# Power.net
KiCad netlist of a schematic drawn in Altium Designer
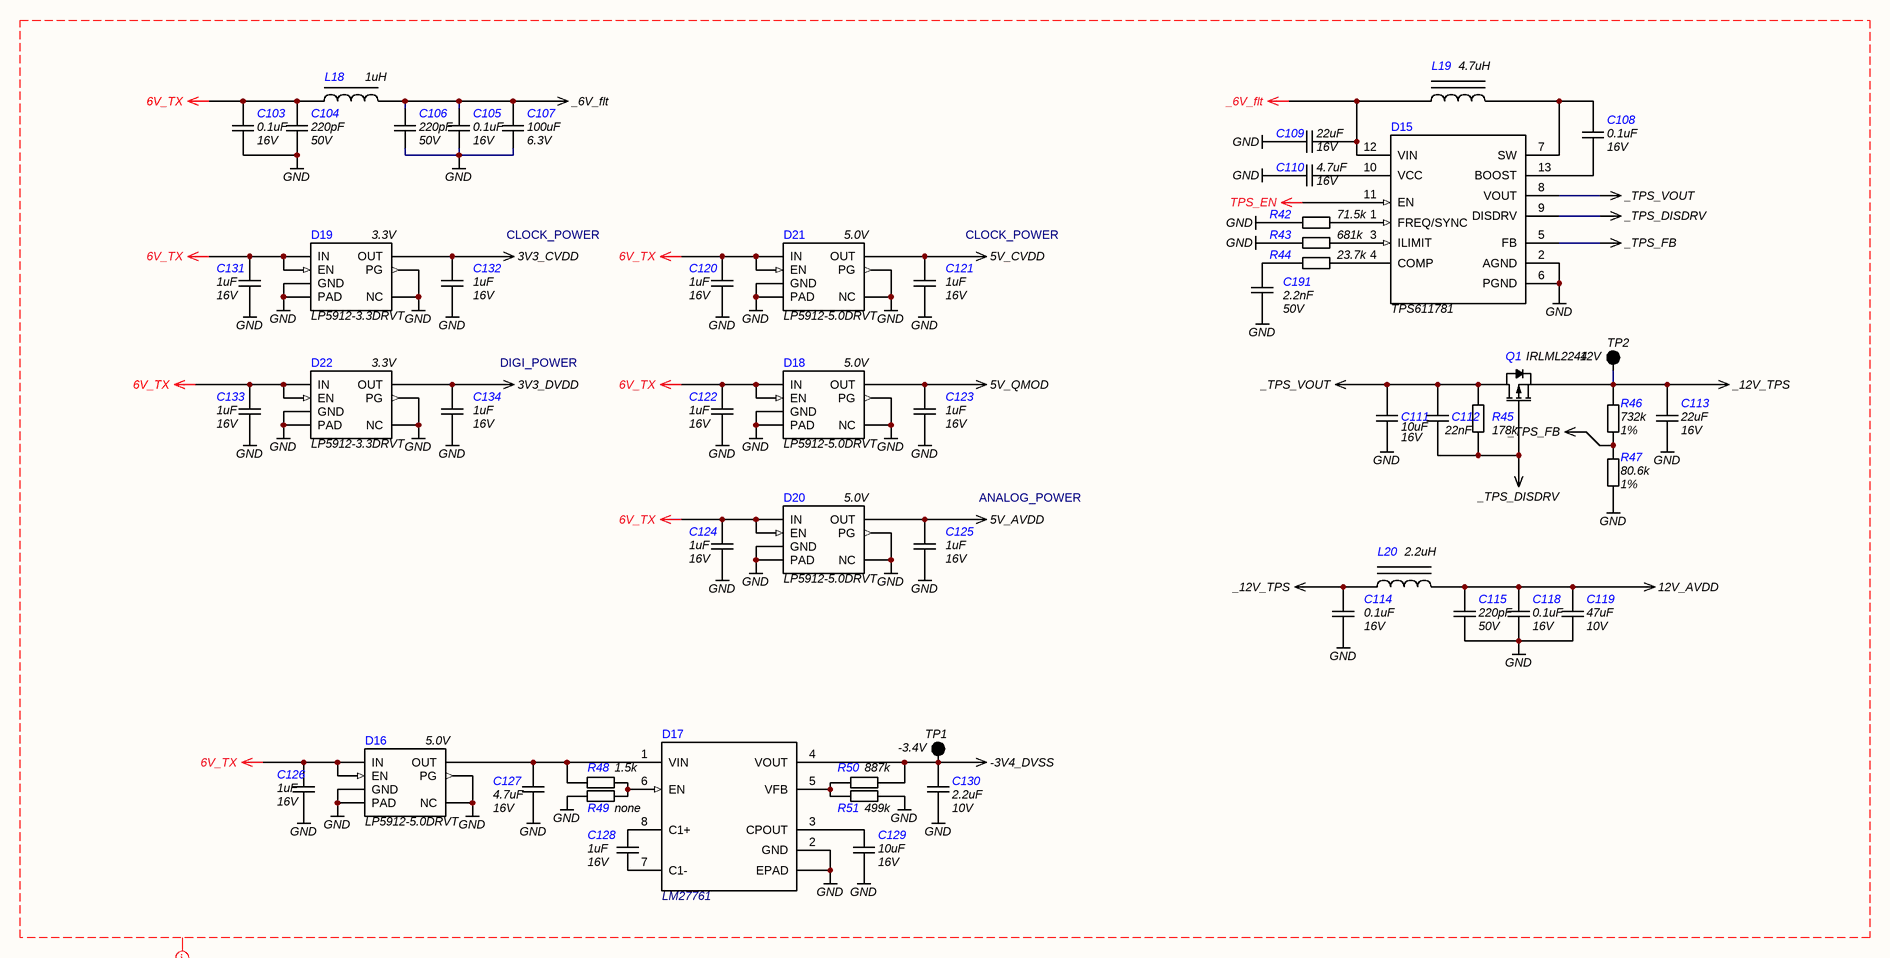
[diagram p0: Power.SchDoc]

(export (version "E")
  (design (tool "Eeschema 10.0.6"))
  (components
    (comp (ref "C103")
      (value "0.1uF")
      (footprint "C0402")
      (description "SMD Capacitor")
      (fields
        (field (name "MANUFACTURER") "Murata")
        (field (name "TOLERANCE") "10%")
        (field (name "VOLTAGE") "16V")
      )
      (libsource (lib "Kintex_SDR") (part "CAP"))
    )
    (comp (ref "C104")
      (value "220pF")
      (footprint "C0603")
      (description "SMD Capacitor")
      (fields
        (field (name "MANUFACTURER") "Kemet")
        (field (name "TOLERANCE") "10%")
        (field (name "VOLTAGE") "50V")
      )
      (libsource (lib "Kintex_SDR") (part "CAP"))
    )
    (comp (ref "C105")
      (value "0.1uF")
      (footprint "C0402")
      (description "SMD Capacitor")
      (fields
        (field (name "MANUFACTURER") "Murata")
        (field (name "TOLERANCE") "10%")
        (field (name "VOLTAGE") "16V")
      )
      (libsource (lib "Kintex_SDR") (part "CAP"))
    )
    (comp (ref "C106")
      (value "220pF")
      (footprint "C0603")
      (description "SMD Capacitor")
      (fields
        (field (name "MANUFACTURER") "Kemet")
        (field (name "TOLERANCE") "10%")
        (field (name "VOLTAGE") "50V")
      )
      (libsource (lib "Kintex_SDR") (part "CAP"))
    )
    (comp (ref "C107")
      (value "100uF")
      (footprint "C1210")
      (description "SMD Capacitor")
      (fields
        (field (name "MANUFACTURER") "Murata")
        (field (name "TOLERANCE") "20%")
        (field (name "VOLTAGE") "6.3V")
      )
      (libsource (lib "Kintex_SDR") (part "CAP uF"))
    )
    (comp (ref "C108")
      (value "0.1uF")
      (footprint "C0402")
      (description "SMD Capacitor")
      (fields
        (field (name "MANUFACTURER") "Murata")
        (field (name "TOLERANCE") "10%")
        (field (name "VOLTAGE") "16V")
      )
      (libsource (lib "Kintex_SDR") (part "CAP"))
    )
    (comp (ref "C109")
      (value "22uF")
      (footprint "C0805")
      (description "SMD Capacitor")
      (fields
        (field (name "MANUFACTURER") "Murata")
        (field (name "TOLERANCE") "±20%")
        (field (name "VOLTAGE") "16V")
      )
      (libsource (lib "Kintex_SDR") (part "CAP uF"))
    )
    (comp (ref "C110")
      (value "4.7uF")
      (footprint "C0603")
      (description "SMD Capacitor")
      (fields
        (field (name "MANUFACTURER") "Samsung")
        (field (name "TOLERANCE") "10%")
        (field (name "VOLTAGE") "16V")
      )
      (libsource (lib "Kintex_SDR") (part "CAP"))
    )
    (comp (ref "C111")
      (value "10uF")
      (footprint "C0805")
      (description "SMD Capacitor")
      (fields
        (field (name "MANUFACTURER") "Murata")
        (field (name "TOLERANCE") "±10%")
        (field (name "VOLTAGE") "16V")
      )
      (libsource (lib "Kintex_SDR") (part "CAP uF"))
    )
    (comp (ref "C112")
      (value "22nF")
      (footprint "C0402")
      (description "SMD Capacitor")
      (fields (field (name "MANUFACTURER") "Murata") (field (name "TOLERANCE") "10%"))
      (libsource (lib "Kintex_SDR") (part "CAP"))
    )
    (comp (ref "C113")
      (value "22uF")
      (footprint "C0805")
      (description "SMD Capacitor")
      (fields
        (field (name "MANUFACTURER") "Murata")
        (field (name "TOLERANCE") "±20%")
        (field (name "VOLTAGE") "16V")
      )
      (libsource (lib "Kintex_SDR") (part "CAP uF"))
    )
    (comp (ref "C114")
      (value "0.1uF")
      (footprint "C0402")
      (description "SMD Capacitor")
      (fields
        (field (name "MANUFACTURER") "Murata")
        (field (name "TOLERANCE") "10%")
        (field (name "VOLTAGE") "16V")
      )
      (libsource (lib "Kintex_SDR") (part "CAP"))
    )
    (comp (ref "C115")
      (value "220pF")
      (footprint "C0603")
      (description "SMD Capacitor")
      (fields
        (field (name "MANUFACTURER") "Kemet")
        (field (name "TOLERANCE") "10%")
        (field (name "VOLTAGE") "50V")
      )
      (libsource (lib "Kintex_SDR") (part "CAP"))
    )
    (comp (ref "C118")
      (value "0.1uF")
      (footprint "C0402")
      (description "SMD Capacitor")
      (fields
        (field (name "MANUFACTURER") "Murata")
        (field (name "TOLERANCE") "10%")
        (field (name "VOLTAGE") "16V")
      )
      (libsource (lib "Kintex_SDR") (part "CAP"))
    )
    (comp (ref "C119")
      (value "47uF")
      (footprint "C1210")
      (description "SMD Capacitor")
      (fields
        (field (name "MANUFACTURER") "Murata")
        (field (name "TOLERANCE") "10%")
        (field (name "VOLTAGE") "10V")
      )
      (libsource (lib "Kintex_SDR") (part "CAP uF"))
    )
    (comp (ref "C120")
      (value "1uF")
      (footprint "C0603")
      (description "SMD Capacitor")
      (fields
        (field (name "MANUFACTURER") "Kemet")
        (field (name "TOLERANCE") "10%")
        (field (name "VOLTAGE") "16V")
      )
      (libsource (lib "Kintex_SDR") (part "CAP"))
    )
    (comp (ref "C121")
      (value "1uF")
      (footprint "C0603")
      (description "SMD Capacitor")
      (fields
        (field (name "MANUFACTURER") "Kemet")
        (field (name "TOLERANCE") "10%")
        (field (name "VOLTAGE") "16V")
      )
      (libsource (lib "Kintex_SDR") (part "CAP"))
    )
    (comp (ref "C122")
      (value "1uF")
      (footprint "C0603")
      (description "SMD Capacitor")
      (fields
        (field (name "MANUFACTURER") "Kemet")
        (field (name "TOLERANCE") "10%")
        (field (name "VOLTAGE") "16V")
      )
      (libsource (lib "Kintex_SDR") (part "CAP"))
    )
    (comp (ref "C123")
      (value "1uF")
      (footprint "C0603")
      (description "SMD Capacitor")
      (fields
        (field (name "MANUFACTURER") "Kemet")
        (field (name "TOLERANCE") "10%")
        (field (name "VOLTAGE") "16V")
      )
      (libsource (lib "Kintex_SDR") (part "CAP"))
    )
    (comp (ref "C124")
      (value "1uF")
      (footprint "C0603")
      (description "SMD Capacitor")
      (fields
        (field (name "MANUFACTURER") "Kemet")
        (field (name "TOLERANCE") "10%")
        (field (name "VOLTAGE") "16V")
      )
      (libsource (lib "Kintex_SDR") (part "CAP"))
    )
    (comp (ref "C125")
      (value "1uF")
      (footprint "C0603")
      (description "SMD Capacitor")
      (fields
        (field (name "MANUFACTURER") "Kemet")
        (field (name "TOLERANCE") "10%")
        (field (name "VOLTAGE") "16V")
      )
      (libsource (lib "Kintex_SDR") (part "CAP"))
    )
    (comp (ref "C126")
      (value "1uF")
      (footprint "C0603")
      (description "SMD Capacitor")
      (fields
        (field (name "MANUFACTURER") "Kemet")
        (field (name "TOLERANCE") "10%")
        (field (name "VOLTAGE") "16V")
      )
      (libsource (lib "Kintex_SDR") (part "CAP"))
    )
    (comp (ref "C127")
      (value "4.7uF")
      (footprint "C0603")
      (description "SMD Capacitor")
      (fields
        (field (name "MANUFACTURER") "Samsung")
        (field (name "TOLERANCE") "10%")
        (field (name "VOLTAGE") "16V")
      )
      (libsource (lib "Kintex_SDR") (part "CAP"))
    )
    (comp (ref "C128")
      (value "1uF")
      (footprint "C0603")
      (description "SMD Capacitor")
      (fields
        (field (name "MANUFACTURER") "Kemet")
        (field (name "TOLERANCE") "10%")
        (field (name "VOLTAGE") "16V")
      )
      (libsource (lib "Kintex_SDR") (part "CAP"))
    )
    (comp (ref "C129")
      (value "10uF")
      (footprint "C0805")
      (description "SMD Capacitor")
      (fields
        (field (name "MANUFACTURER") "Murata")
        (field (name "TOLERANCE") "±10%")
        (field (name "VOLTAGE") "16V")
      )
      (libsource (lib "Kintex_SDR") (part "CAP uF"))
    )
    (comp (ref "C130")
      (value "2.2uF")
      (footprint "C0603")
      (description "SMD Capacitor")
      (fields
        (field (name "MANUFACTURER") "Murata")
        (field (name "TOLERANCE") "10%")
        (field (name "VOLTAGE") "10V")
      )
      (libsource (lib "Kintex_SDR") (part "CAP"))
    )
    (comp (ref "C131")
      (value "1uF")
      (footprint "C0603")
      (description "SMD Capacitor")
      (fields
        (field (name "MANUFACTURER") "Kemet")
        (field (name "TOLERANCE") "10%")
        (field (name "VOLTAGE") "16V")
      )
      (libsource (lib "Kintex_SDR") (part "CAP"))
    )
    (comp (ref "C132")
      (value "1uF")
      (footprint "C0603")
      (description "SMD Capacitor")
      (fields
        (field (name "MANUFACTURER") "Kemet")
        (field (name "TOLERANCE") "10%")
        (field (name "VOLTAGE") "16V")
      )
      (libsource (lib "Kintex_SDR") (part "CAP"))
    )
    (comp (ref "C133")
      (value "1uF")
      (footprint "C0603")
      (description "SMD Capacitor")
      (fields
        (field (name "MANUFACTURER") "Kemet")
        (field (name "TOLERANCE") "10%")
        (field (name "VOLTAGE") "16V")
      )
      (libsource (lib "Kintex_SDR") (part "CAP"))
    )
    (comp (ref "C134")
      (value "1uF")
      (footprint "C0603")
      (description "SMD Capacitor")
      (fields
        (field (name "MANUFACTURER") "Kemet")
        (field (name "TOLERANCE") "10%")
        (field (name "VOLTAGE") "16V")
      )
      (libsource (lib "Kintex_SDR") (part "CAP"))
    )
    (comp (ref "C191")
      (value "2.2nF")
      (footprint "C0603")
      (description "SMD Capacitor")
      (fields
        (field (name "MANUFACTURER") "Murata")
        (field (name "TOLERANCE") "±5%")
        (field (name "VOLTAGE") "50V")
      )
      (libsource (lib "Kintex_SDR") (part "CAP"))
    )
    (comp (ref "D15")
      (value "TPS611781")
      (footprint "DBLib:TPS611781x")
      (description "10-A Fully-Integrated Synchronous Boost with Load Disconnect Control")
      (fields (field (name "MANUFACTURER") "Texas Instruments") (field (name "VOLTAGE") "4.5 V to 20 V"))
      (libsource (lib "DBLib") (part "TPS611781"))
    )
    (comp (ref "D16")
      (value "LP5912")
      (footprint "DBLib:WSON-6")
      (description "LP5912 500-mA Low-Noise, Low-IQ LDO")
      (fields
        (field (name "MANUFACTURER") "Texas Instruments")
        (field (name "NAME") "LP5912-5.0DRVT")
        (field (name "VOLTAGE") "5.0V")
      )
      (libsource (lib "DBLib") (part "LP5912"))
    )
    (comp (ref "D17")
      (value "LM27761")
      (footprint "DBLib:WSON-8")
      (description "Low-Noise, Regulated, Switched-Capacitor Voltage Inverter")
      (fields (field (name "MANUFACTURER") "Texas Instruments") (field (name "VOLTAGE") "2.7 V to 5.5"))
      (libsource (lib "DBLib") (part "LM27761"))
    )
    (comp (ref "D18")
      (value "LP5912")
      (footprint "DBLib:WSON-6")
      (description "LP5912 500-mA Low-Noise, Low-IQ LDO")
      (fields
        (field (name "MANUFACTURER") "Texas Instruments")
        (field (name "NAME") "LP5912-5.0DRVT")
        (field (name "VOLTAGE") "5.0V")
      )
      (libsource (lib "DBLib") (part "LP5912"))
    )
    (comp (ref "D19")
      (value "LP5912")
      (footprint "DBLib:WSON-6")
      (description "LP5912 500-mA Low-Noise, Low-IQ LDO")
      (fields
        (field (name "MANUFACTURER") "Texas Instruments")
        (field (name "NAME") "LP5912-3.3DRVT")
        (field (name "VOLTAGE") "3.3V")
      )
      (libsource (lib "DBLib") (part "LP5912"))
    )
    (comp (ref "D20")
      (value "LP5912")
      (footprint "DBLib:WSON-6")
      (description "LP5912 500-mA Low-Noise, Low-IQ LDO")
      (fields
        (field (name "MANUFACTURER") "Texas Instruments")
        (field (name "NAME") "LP5912-5.0DRVT")
        (field (name "VOLTAGE") "5.0V")
      )
      (libsource (lib "DBLib") (part "LP5912"))
    )
    (comp (ref "D21")
      (value "LP5912")
      (footprint "DBLib:WSON-6")
      (description "LP5912 500-mA Low-Noise, Low-IQ LDO")
      (fields
        (field (name "MANUFACTURER") "Texas Instruments")
        (field (name "NAME") "LP5912-5.0DRVT")
        (field (name "VOLTAGE") "5.0V")
      )
      (libsource (lib "DBLib") (part "LP5912"))
    )
    (comp (ref "D22")
      (value "LP5912")
      (footprint "DBLib:WSON-6")
      (description "LP5912 500-mA Low-Noise, Low-IQ LDO")
      (fields
        (field (name "MANUFACTURER") "Texas Instruments")
        (field (name "NAME") "LP5912-3.3DRVT")
        (field (name "VOLTAGE") "3.3V")
      )
      (libsource (lib "DBLib") (part "LP5912"))
    )
    (comp (ref "L18")
      (value "1uH")
      (footprint "L1210_Murata LQH")
      (description "Inductor Power Lines")
      (fields (field (name "MANUFACTURER") "Murata") (field (name "TOLERANCE") "5%"))
      (libsource (lib "Kintex_SDR") (part "Inductor LF"))
    )
    (comp (ref "L19")
      (value "4.7uH")
      (footprint "XAL4030")
      (description "Magnetic-Core Inductor")
      (fields (field (name "MANUFACTURER") "Coilcraft") (field (name "TOLERANCE") "±30%"))
      (libsource (lib "Kintex_SDR") (part "Inductor PWR"))
    )
    (comp (ref "L20")
      (value "2.2uH")
      (footprint "XAL4020")
      (description "Magnetic-Core Inductor")
      (fields (field (name "MANUFACTURER") "Coilcraft") (field (name "TOLERANCE") "±30%"))
      (libsource (lib "Kintex_SDR") (part "Inductor PWR"))
    )
    (comp (ref "Q1")
      (value "IRLML2244")
      (footprint "DBLib:SOT-23")
      (description "P-Channel MOSFET")
      (fields (field (name "VOLTAGE") "-20V"))
      (libsource (lib "DBLib") (part "IRLML2244"))
    )
    (comp (ref "R42")
      (value "71.5k")
      (footprint "R0402")
      (description "SMD Resistor")
      (fields (field (name "POWER") "0.063 Wt") (field (name "TOLERANCE") "1%"))
      (libsource (lib "") (part "RES_2"))
    )
    (comp (ref "R43")
      (value "681k")
      (footprint "R0402")
      (description "SMD Resistor")
      (fields (field (name "POWER") "0.063 Wt") (field (name "TOLERANCE") "1%"))
      (libsource (lib "") (part "RES_2"))
    )
    (comp (ref "R44")
      (value "23.7k")
      (footprint "R0603")
      (description "SMD Resistor")
      (fields (field (name "POWER") "0.1 Wt") (field (name "TOLERANCE") "1%"))
      (libsource (lib "") (part "RES_2"))
    )
    (comp (ref "R45")
      (value "178k")
      (footprint "R0402")
      (description "SMD Resistor")
      (fields (field (name "POWER") "0.063 Wt") (field (name "TOLERANCE") "1%"))
      (libsource (lib "") (part "RES_1"))
    )
    (comp (ref "R46")
      (value "732k")
      (footprint "R0402")
      (description "SMD Resistor")
      (fields
        (field (name "POWER") "0.063 Wt")
        (field (name "TOLERANCE") "1%")
        (field (name "MANUFACTURER") "Panasonic Electronic Components")
      )
      (libsource (lib "") (part "RES_1"))
    )
    (comp (ref "R47")
      (value "80.6k")
      (footprint "R0402")
      (description "SMD Resistor")
      (fields
        (field (name "POWER") "0.063 Wt")
        (field (name "TOLERANCE") "1%")
        (field (name "MANUFACTURER") "Panasonic Electronic Components")
      )
      (libsource (lib "") (part "RES_1"))
    )
    (comp (ref "R48")
      (value "1.5k")
      (footprint "R0402")
      (description "SMD Resistor")
      (fields (field (name "POWER") "0.063 Wt") (field (name "TOLERANCE") "0.5%"))
      (libsource (lib "Kintex_SDR") (part "RES"))
    )
    (comp (ref "R49")
      (value "none")
      (footprint "R0402")
      (description "SMD Resistor")
      (fields (field (name "POWER") "0.1 Wt") (field (name "TOLERANCE") "1%"))
      (libsource (lib "") (part "RES_2"))
    )
    (comp (ref "R50")
      (value "887k")
      (footprint "R0402")
      (description "SMD Resistor")
      (fields (field (name "POWER") "0.1 Wt") (field (name "TOLERANCE") "±1%"))
      (libsource (lib "") (part "RES_2"))
    )
    (comp (ref "R51")
      (value "499k")
      (footprint "R0402")
      (description "SMD Resistor")
      (fields (field (name "POWER") "0.1 Wt") (field (name "TOLERANCE") "±1%"))
      (libsource (lib "") (part "RES_2"))
    )
    (comp (ref "TP1")
      (value "-3.4V")
      (footprint "Control Point")
      (libsource (lib "Kintex_SDR") (part "Test  Point"))
    )
    (comp (ref "TP2")
      (value "12V")
      (footprint "Control Point")
      (libsource (lib "Kintex_SDR") (part "Test  Point"))
    )
  )
  (nets
    (net (code "1") (name "-3V4_DVSS") (class "Default")
      (node (ref "C130") (pin "1") (pinfunction "1_1") (pintype "passive"))
      (node (ref "D17") (pin "4") (pinfunction "VOUT_4") (pintype "passive"))
      (node (ref "R50") (pin "2") (pinfunction "2_2") (pintype "passive"))
      (node (ref "TP1") (pin "1") (pinfunction "1_1") (pintype "passive"))
    )
    (net (code "2") (name "3V3_CVDD") (class "Default")
      (node (ref "C132") (pin "1") (pinfunction "1_1") (pintype "passive"))
      (node (ref "D19") (pin "1") (pinfunction "OUT_1") (pintype "passive"))
    )
    (net (code "3") (name "3V3_DVDD") (class "Default")
      (node (ref "C134") (pin "1") (pinfunction "1_1") (pintype "passive"))
      (node (ref "D22") (pin "1") (pinfunction "OUT_1") (pintype "passive"))
    )
    (net (code "4") (name "5V_AVDD") (class "Default")
      (node (ref "C125") (pin "1") (pinfunction "1_1") (pintype "passive"))
      (node (ref "D20") (pin "1") (pinfunction "OUT_1") (pintype "passive"))
    )
    (net (code "5") (name "5V_CVDD") (class "Default")
      (node (ref "C121") (pin "1") (pinfunction "1_1") (pintype "passive"))
      (node (ref "D21") (pin "1") (pinfunction "OUT_1") (pintype "passive"))
    )
    (net (code "6") (name "5V_QMOD") (class "Default")
      (node (ref "C123") (pin "1") (pinfunction "1_1") (pintype "passive"))
      (node (ref "D18") (pin "1") (pinfunction "OUT_1") (pintype "passive"))
    )
    (net (code "7") (name "6V_TX") (class "Default")
      (node (ref "C103") (pin "2") (pinfunction "2_2") (pintype "passive"))
      (node (ref "C104") (pin "2") (pinfunction "2_2") (pintype "passive"))
      (node (ref "C120") (pin "1") (pinfunction "1_1") (pintype "passive"))
      (node (ref "C122") (pin "1") (pinfunction "1_1") (pintype "passive"))
      (node (ref "C124") (pin "1") (pinfunction "1_1") (pintype "passive"))
      (node (ref "C126") (pin "1") (pinfunction "1_1") (pintype "passive"))
      (node (ref "C131") (pin "1") (pinfunction "1_1") (pintype "passive"))
      (node (ref "C133") (pin "1") (pinfunction "1_1") (pintype "passive"))
      (node (ref "D16") (pin "4") (pinfunction "EN_4") (pintype "input"))
      (node (ref "D16") (pin "6") (pinfunction "IN_6") (pintype "passive"))
      (node (ref "D18") (pin "4") (pinfunction "EN_4") (pintype "input"))
      (node (ref "D18") (pin "6") (pinfunction "IN_6") (pintype "passive"))
      (node (ref "D19") (pin "4") (pinfunction "EN_4") (pintype "input"))
      (node (ref "D19") (pin "6") (pinfunction "IN_6") (pintype "passive"))
      (node (ref "D20") (pin "4") (pinfunction "EN_4") (pintype "input"))
      (node (ref "D20") (pin "6") (pinfunction "IN_6") (pintype "passive"))
      (node (ref "D21") (pin "4") (pinfunction "EN_4") (pintype "input"))
      (node (ref "D21") (pin "6") (pinfunction "IN_6") (pintype "passive"))
      (node (ref "D22") (pin "4") (pinfunction "EN_4") (pintype "input"))
      (node (ref "D22") (pin "6") (pinfunction "IN_6") (pintype "passive"))
      (node (ref "L18") (pin "1") (pinfunction "1_1") (pintype "passive"))
    )
    (net (code "8") (name "12V_AVDD") (class "Default")
      (node (ref "C115") (pin "2") (pinfunction "2_2") (pintype "passive"))
      (node (ref "C118") (pin "2") (pinfunction "2_2") (pintype "passive"))
      (node (ref "C119") (pin "2") (pinfunction "2_2") (pintype "passive"))
      (node (ref "L20") (pin "2") (pinfunction "2_2") (pintype "passive"))
    )
    (net (code "9") (name "GND") (class "Default")
      (node (ref "C103") (pin "1") (pinfunction "1_1") (pintype "passive"))
      (node (ref "C104") (pin "1") (pinfunction "1_1") (pintype "passive"))
      (node (ref "C105") (pin "1") (pinfunction "1_1") (pintype "passive"))
      (node (ref "C106") (pin "1") (pinfunction "1_1") (pintype "passive"))
      (node (ref "C107") (pin "1") (pinfunction "1_1") (pintype "passive"))
      (node (ref "C109") (pin "2") (pinfunction "2_2") (pintype "passive"))
      (node (ref "C110") (pin "2") (pinfunction "2_2") (pintype "passive"))
      (node (ref "C111") (pin "1") (pinfunction "1_1") (pintype "passive"))
      (node (ref "C113") (pin "1") (pinfunction "1_1") (pintype "passive"))
      (node (ref "C114") (pin "1") (pinfunction "1_1") (pintype "passive"))
      (node (ref "C115") (pin "1") (pinfunction "1_1") (pintype "passive"))
      (node (ref "C118") (pin "1") (pinfunction "1_1") (pintype "passive"))
      (node (ref "C119") (pin "1") (pinfunction "1_1") (pintype "passive"))
      (node (ref "C120") (pin "2") (pinfunction "2_2") (pintype "passive"))
      (node (ref "C121") (pin "2") (pinfunction "2_2") (pintype "passive"))
      (node (ref "C122") (pin "2") (pinfunction "2_2") (pintype "passive"))
      (node (ref "C123") (pin "2") (pinfunction "2_2") (pintype "passive"))
      (node (ref "C124") (pin "2") (pinfunction "2_2") (pintype "passive"))
      (node (ref "C125") (pin "2") (pinfunction "2_2") (pintype "passive"))
      (node (ref "C126") (pin "2") (pinfunction "2_2") (pintype "passive"))
      (node (ref "C127") (pin "2") (pinfunction "2_2") (pintype "passive"))
      (node (ref "C129") (pin "2") (pinfunction "2_2") (pintype "passive"))
      (node (ref "C130") (pin "2") (pinfunction "2_2") (pintype "passive"))
      (node (ref "C131") (pin "2") (pinfunction "2_2") (pintype "passive"))
      (node (ref "C132") (pin "2") (pinfunction "2_2") (pintype "passive"))
      (node (ref "C133") (pin "2") (pinfunction "2_2") (pintype "passive"))
      (node (ref "C134") (pin "2") (pinfunction "2_2") (pintype "passive"))
      (node (ref "C191") (pin "1") (pinfunction "1_1") (pintype "passive"))
      (node (ref "D15") (pin "2") (pinfunction "AGND_2") (pintype "passive"))
      (node (ref "D15") (pin "6") (pinfunction "PGND_6") (pintype "passive"))
      (node (ref "D16") (pin "0") (pinfunction "PAD_0") (pintype "passive"))
      (node (ref "D16") (pin "2") (pinfunction "NC_2") (pintype "passive"))
      (node (ref "D16") (pin "3") (pinfunction "PG_3") (pintype "output"))
      (node (ref "D16") (pin "5") (pinfunction "GND_5") (pintype "passive"))
      (node (ref "D17") (pin "0") (pinfunction "EPAD_0") (pintype "passive"))
      (node (ref "D17") (pin "2") (pinfunction "GND_2") (pintype "passive"))
      (node (ref "D18") (pin "0") (pinfunction "PAD_0") (pintype "passive"))
      (node (ref "D18") (pin "2") (pinfunction "NC_2") (pintype "passive"))
      (node (ref "D18") (pin "3") (pinfunction "PG_3") (pintype "output"))
      (node (ref "D18") (pin "5") (pinfunction "GND_5") (pintype "passive"))
      (node (ref "D19") (pin "0") (pinfunction "PAD_0") (pintype "passive"))
      (node (ref "D19") (pin "2") (pinfunction "NC_2") (pintype "passive"))
      (node (ref "D19") (pin "3") (pinfunction "PG_3") (pintype "output"))
      (node (ref "D19") (pin "5") (pinfunction "GND_5") (pintype "passive"))
      (node (ref "D20") (pin "0") (pinfunction "PAD_0") (pintype "passive"))
      (node (ref "D20") (pin "2") (pinfunction "NC_2") (pintype "passive"))
      (node (ref "D20") (pin "3") (pinfunction "PG_3") (pintype "output"))
      (node (ref "D20") (pin "5") (pinfunction "GND_5") (pintype "passive"))
      (node (ref "D21") (pin "0") (pinfunction "PAD_0") (pintype "passive"))
      (node (ref "D21") (pin "2") (pinfunction "NC_2") (pintype "passive"))
      (node (ref "D21") (pin "3") (pinfunction "PG_3") (pintype "output"))
      (node (ref "D21") (pin "5") (pinfunction "GND_5") (pintype "passive"))
      (node (ref "D22") (pin "0") (pinfunction "PAD_0") (pintype "passive"))
      (node (ref "D22") (pin "2") (pinfunction "NC_2") (pintype "passive"))
      (node (ref "D22") (pin "3") (pinfunction "PG_3") (pintype "output"))
      (node (ref "D22") (pin "5") (pinfunction "GND_5") (pintype "passive"))
      (node (ref "R42") (pin "1") (pinfunction "1_1") (pintype "passive"))
      (node (ref "R43") (pin "1") (pinfunction "1_1") (pintype "passive"))
      (node (ref "R47") (pin "1") (pinfunction "1_1") (pintype "passive"))
      (node (ref "R49") (pin "1") (pinfunction "1_1") (pintype "passive"))
      (node (ref "R51") (pin "2") (pinfunction "2_2") (pintype "passive"))
    )
    (net (code "10") (name "Net-(C191-Pad2)") (class "Default")
      (node (ref "C191") (pin "2") (pinfunction "2_2") (pintype "passive"))
      (node (ref "R44") (pin "1") (pinfunction "1_1") (pintype "passive"))
    )
    (net (code "11") (name "Net-(D15-BOOST)") (class "Default")
      (node (ref "C108") (pin "1") (pinfunction "1_1") (pintype "passive"))
      (node (ref "D15") (pin "13") (pinfunction "BOOST_13") (pintype "passive"))
    )
    (net (code "12") (name "Net-(D15-COMP)") (class "Default")
      (node (ref "D15") (pin "4") (pinfunction "COMP_4") (pintype "passive"))
      (node (ref "R44") (pin "2") (pinfunction "2_2") (pintype "passive"))
    )
    (net (code "13") (name "Net-(D15-FREQ{slash}SYNC)") (class "Default")
      (node (ref "D15") (pin "1") (pinfunction "FREQ/SYNC_1") (pintype "input"))
      (node (ref "R42") (pin "2") (pinfunction "2_2") (pintype "passive"))
    )
    (net (code "14") (name "Net-(D15-ILIMIT)") (class "Default")
      (node (ref "D15") (pin "3") (pinfunction "ILIMIT_3") (pintype "input"))
      (node (ref "R43") (pin "2") (pinfunction "2_2") (pintype "passive"))
    )
    (net (code "15") (name "Net-(D15-SW)") (class "Default")
      (node (ref "C108") (pin "2") (pinfunction "2_2") (pintype "passive"))
      (node (ref "D15") (pin "7") (pinfunction "SW_7") (pintype "passive"))
      (node (ref "L19") (pin "2") (pinfunction "2_2") (pintype "passive"))
    )
    (net (code "16") (name "Net-(D15-VCC)") (class "Default")
      (node (ref "C110") (pin "1") (pinfunction "1_1") (pintype "passive"))
      (node (ref "D15") (pin "10") (pinfunction "VCC_10") (pintype "passive"))
    )
    (net (code "17") (name "Net-(D16-OUT)") (class "Default")
      (node (ref "C127") (pin "1") (pinfunction "1_1") (pintype "passive"))
      (node (ref "D16") (pin "1") (pinfunction "OUT_1") (pintype "passive"))
      (node (ref "D17") (pin "1") (pinfunction "VIN_1") (pintype "passive"))
      (node (ref "R48") (pin "2") (pinfunction "2_2") (pintype "passive"))
    )
    (net (code "18") (name "Net-(D17-C1+)") (class "Default")
      (node (ref "C128") (pin "2") (pinfunction "2_2") (pintype "passive"))
      (node (ref "D17") (pin "8") (pinfunction "C1+_8") (pintype "passive"))
    )
    (net (code "19") (name "Net-(D17-C1-)") (class "Default")
      (node (ref "C128") (pin "1") (pinfunction "1_1") (pintype "passive"))
      (node (ref "D17") (pin "7") (pinfunction "C1-_7") (pintype "passive"))
    )
    (net (code "20") (name "Net-(D17-CPOUT)") (class "Default")
      (node (ref "C129") (pin "1") (pinfunction "1_1") (pintype "passive"))
      (node (ref "D17") (pin "3") (pinfunction "CPOUT_3") (pintype "passive"))
    )
    (net (code "21") (name "Net-(D17-EN)") (class "Default")
      (node (ref "D17") (pin "6") (pinfunction "EN_6") (pintype "input"))
      (node (ref "R48") (pin "1") (pinfunction "1_1") (pintype "passive"))
      (node (ref "R49") (pin "2") (pinfunction "2_2") (pintype "passive"))
    )
    (net (code "22") (name "Net-(D17-VFB)") (class "Default")
      (node (ref "D17") (pin "5") (pinfunction "VFB_5") (pintype "passive"))
      (node (ref "R50") (pin "1") (pinfunction "1_1") (pintype "passive"))
      (node (ref "R51") (pin "1") (pinfunction "1_1") (pintype "passive"))
    )
    (net (code "23") (name "TPS_EN") (class "Default")
      (node (ref "D15") (pin "11") (pinfunction "EN_11") (pintype "input"))
    )
    (net (code "24") (name "_6V_flt") (class "Default")
      (node (ref "C105") (pin "2") (pinfunction "2_2") (pintype "passive"))
      (node (ref "C106") (pin "2") (pinfunction "2_2") (pintype "passive"))
      (node (ref "C107") (pin "2") (pinfunction "2_2") (pintype "passive"))
      (node (ref "C109") (pin "1") (pinfunction "1_1") (pintype "passive"))
      (node (ref "D15") (pin "12") (pinfunction "VIN_12") (pintype "passive"))
      (node (ref "L18") (pin "2") (pinfunction "2_2") (pintype "passive"))
      (node (ref "L19") (pin "1") (pinfunction "1_1") (pintype "passive"))
    )
    (net (code "25") (name "_12V_TPS") (class "Default")
      (node (ref "C113") (pin "2") (pinfunction "2_2") (pintype "passive"))
      (node (ref "C114") (pin "2") (pinfunction "2_2") (pintype "passive"))
      (node (ref "L20") (pin "1") (pinfunction "1_1") (pintype "passive"))
      (node (ref "Q1") (pin "2") (pinfunction "S_2") (pintype "passive"))
      (node (ref "R46") (pin "2") (pinfunction "2_2") (pintype "passive"))
      (node (ref "TP2") (pin "1") (pinfunction "1_1") (pintype "passive"))
    )
    (net (code "26") (name "_TPS_DISDRV") (class "Default")
      (node (ref "C112") (pin "2") (pinfunction "2_2") (pintype "passive"))
      (node (ref "D15") (pin "9") (pinfunction "DISDRV_9") (pintype "passive"))
      (node (ref "Q1") (pin "1") (pinfunction "G_1") (pintype "passive"))
      (node (ref "R45") (pin "1") (pinfunction "1_1") (pintype "passive"))
    )
    (net (code "27") (name "_TPS_FB") (class "Default")
      (node (ref "D15") (pin "5") (pinfunction "FB_5") (pintype "passive"))
      (node (ref "R46") (pin "1") (pinfunction "1_1") (pintype "passive"))
      (node (ref "R47") (pin "2") (pinfunction "2_2") (pintype "passive"))
    )
    (net (code "28") (name "_TPS_VOUT") (class "Default")
      (node (ref "C111") (pin "2") (pinfunction "2_2") (pintype "passive"))
      (node (ref "C112") (pin "1") (pinfunction "1_1") (pintype "passive"))
      (node (ref "D15") (pin "8") (pinfunction "VOUT_8") (pintype "passive"))
      (node (ref "Q1") (pin "3") (pinfunction "D_3") (pintype "passive"))
      (node (ref "R45") (pin "2") (pinfunction "2_2") (pintype "passive"))
    )
  )
)
